# PCM2904DAC_ADC.net
KiCad netlist of a schematic drawn in EAGLE
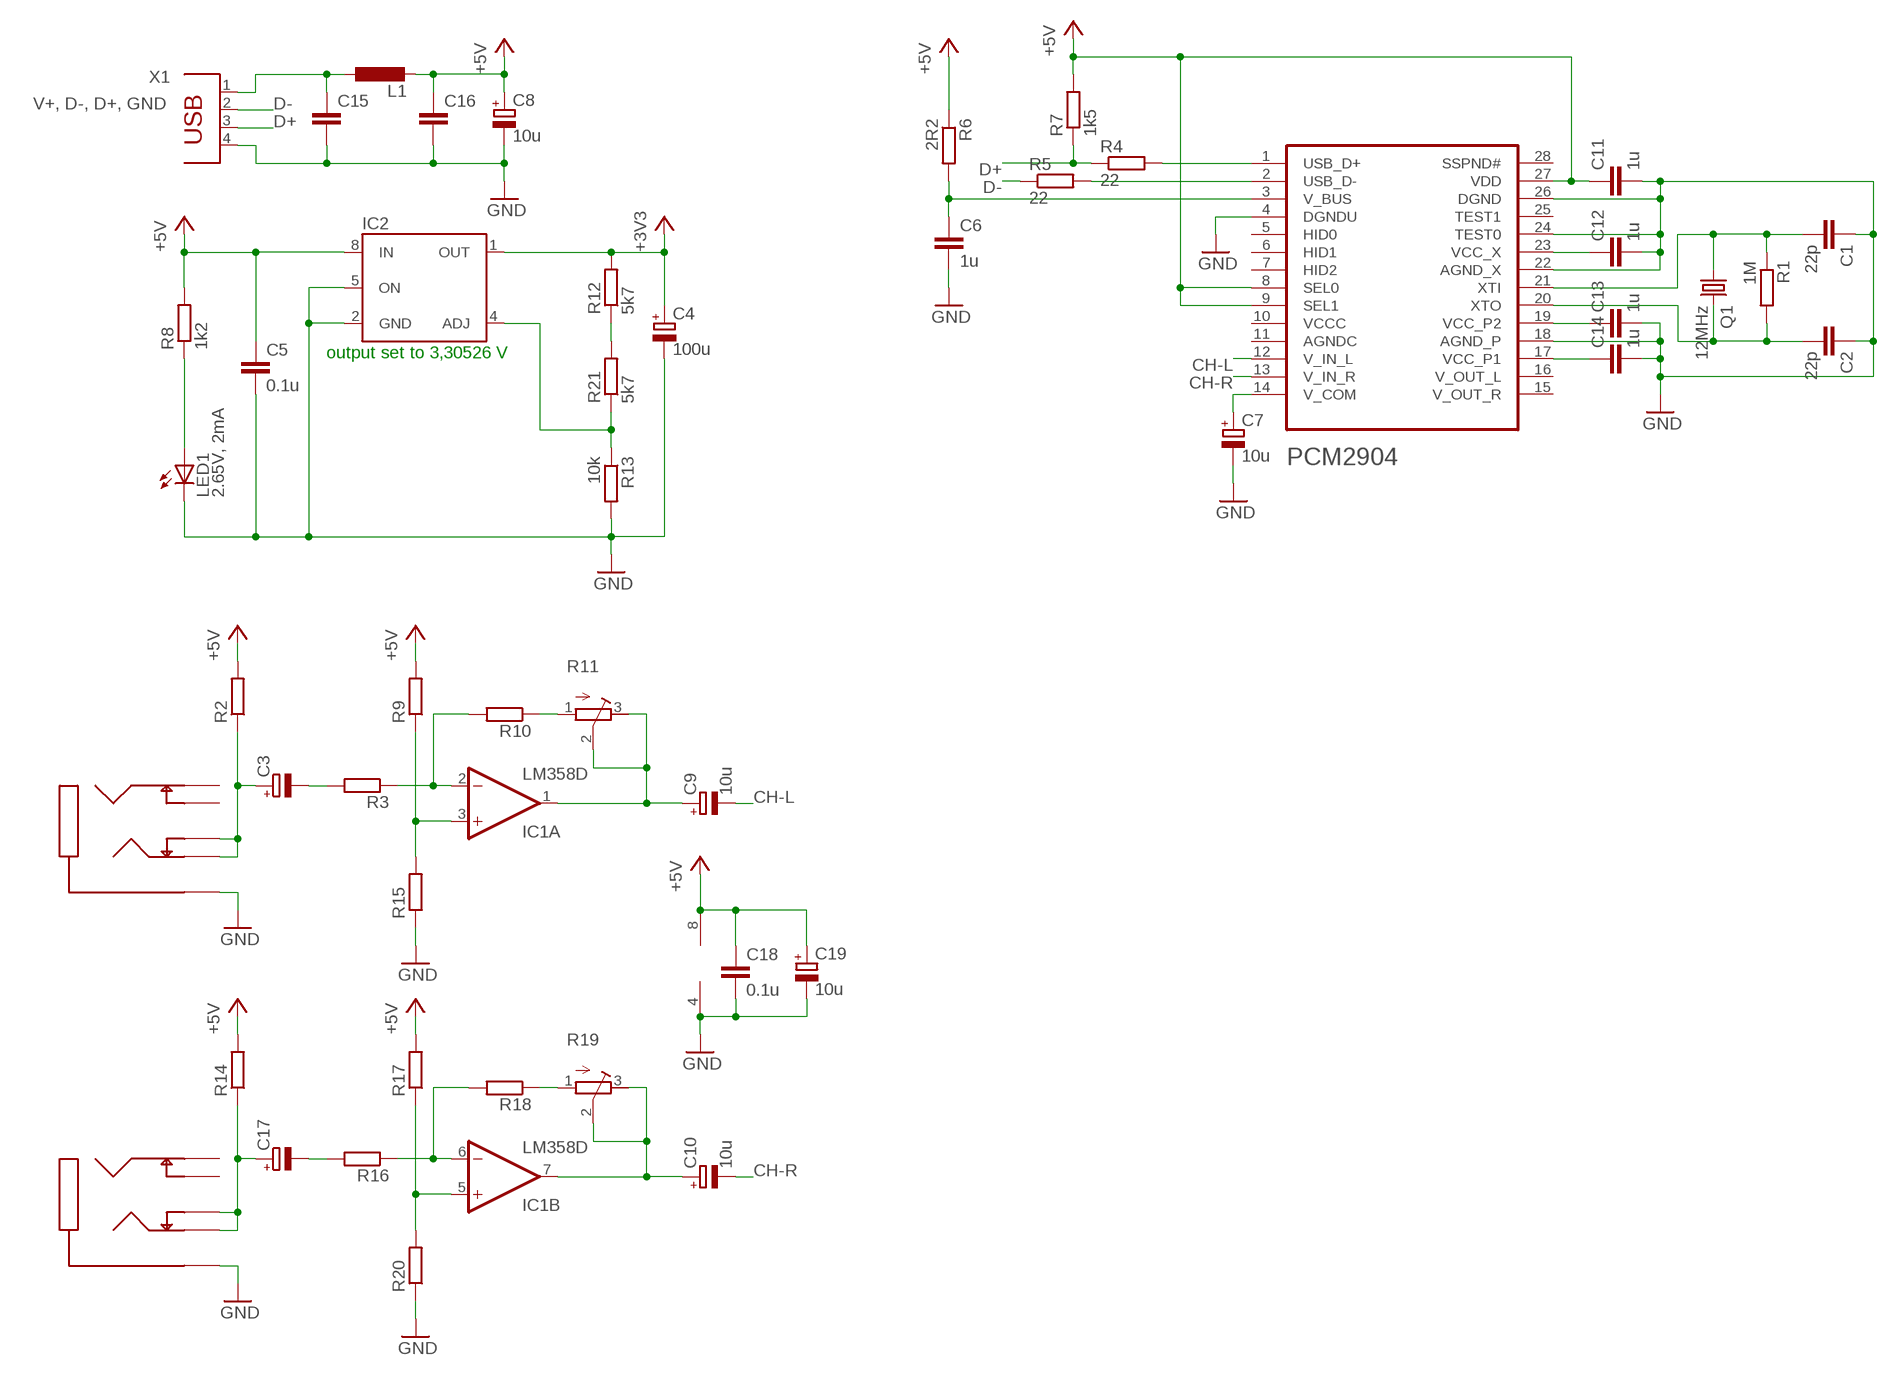
[diagram p0: schematic, sheet 1]

(export (version "E")
  (design (tool "Eeschema 10.0.6"))
  (components
    (comp (ref "C1")
      (value "22p")
      (footprint "eagle-import:C1206")
      (libsource (lib "eagle-import") (part "C-EUC1206"))
    )
    (comp (ref "C2")
      (value "22p")
      (footprint "eagle-import:C1206")
      (libsource (lib "eagle-import") (part "C-EUC1206"))
    )
    (comp (ref "C3")
      (value "CPOL-EU153CLV-0505")
      (footprint "eagle-import:153CLV-0505")
      (libsource (lib "eagle-import") (part "CPOL-EU153CLV-0505"))
    )
    (comp (ref "C4")
      (value "100u")
      (footprint "eagle-import:153CLV-0807")
      (libsource (lib "eagle-import") (part "rcl_334_CPOL-EU153CLV-0807"))
    )
    (comp (ref "C5")
      (value "0.1u")
      (footprint "eagle-import:C1206")
      (libsource (lib "eagle-import") (part "C-EUC1206"))
    )
    (comp (ref "C6")
      (value "1u")
      (footprint "eagle-import:C1206")
      (libsource (lib "eagle-import") (part "C-EUC1206"))
    )
    (comp (ref "C7")
      (value "10u")
      (footprint "eagle-import:153CLV-0505")
      (libsource (lib "eagle-import") (part "rcl_334_CPOL-EU153CLV-0505"))
    )
    (comp (ref "C8")
      (value "10u")
      (footprint "eagle-import:153CLV-0505")
      (libsource (lib "eagle-import") (part "CPOL-EU153CLV-0505"))
    )
    (comp (ref "C9")
      (value "10u")
      (footprint "eagle-import:153CLV-0505")
      (libsource (lib "eagle-import") (part "CPOL-EU153CLV-0505"))
    )
    (comp (ref "C10")
      (value "10u")
      (footprint "eagle-import:153CLV-0505")
      (libsource (lib "eagle-import") (part "rcl_334_CPOL-EU153CLV-0505"))
    )
    (comp (ref "C11")
      (value "1u")
      (footprint "eagle-import:C1206")
      (libsource (lib "eagle-import") (part "C-EUC1206"))
    )
    (comp (ref "C12")
      (value "1u")
      (footprint "eagle-import:C1206")
      (libsource (lib "eagle-import") (part "C-EUC1206"))
    )
    (comp (ref "C13")
      (value "1u")
      (footprint "eagle-import:C1206")
      (libsource (lib "eagle-import") (part "C-EUC1206"))
    )
    (comp (ref "C14")
      (value "1u")
      (footprint "eagle-import:C1206")
      (libsource (lib "eagle-import") (part "C-EUC1206"))
    )
    (comp (ref "C15")
      (value "C-EUC1206K")
      (footprint "eagle-import:C1206K")
      (libsource (lib "eagle-import") (part "rcl_334_C-EUC1206K"))
    )
    (comp (ref "C16")
      (value "C-EUC1206K")
      (footprint "eagle-import:C1206K")
      (libsource (lib "eagle-import") (part "rcl_334_C-EUC1206K"))
    )
    (comp (ref "C17")
      (value "CPOL-EU153CLV-0505")
      (footprint "eagle-import:153CLV-0505")
      (libsource (lib "eagle-import") (part "CPOL-EU153CLV-0505"))
    )
    (comp (ref "C18")
      (value "0.1u")
      (footprint "eagle-import:C1206")
      (libsource (lib "eagle-import") (part "C-EUC1206"))
    )
    (comp (ref "C19")
      (value "10u")
      (footprint "eagle-import:153CLV-0505")
      (libsource (lib "eagle-import") (part "rcl_334_CPOL-EU153CLV-0505"))
    )
    (comp (ref "IC1")
      (value "LM358D")
      (footprint "eagle-import:SO08")
      (libsource (lib "eagle-import") (part "LM358D"))
    )
    (comp (ref "IC2")
      (value "LM2931-ADJM")
      (footprint "eagle-import:SO08")
      (libsource (lib "eagle-import") (part "LM2931-ADJM"))
    )
    (comp (ref "L1")
      (value "L-EU0207/7")
      (footprint "eagle-import:0207_7")
      (libsource (lib "eagle-import") (part "L-EU0207/7"))
    )
    (comp (ref "LED1")
      (value "2.65V, 2mA")
      (footprint "eagle-import:CHIPLED_0805")
      (libsource (lib "eagle-import") (part "LEDCHIPLED_0805"))
    )
    (comp (ref "PCM2904")
      (value "PCM2904")
      (footprint "eagle-import:SSOP28")
      (libsource (lib "eagle-import") (part "PCM2904"))
    )
    (comp (ref "Q1")
      (value "12MHz")
      (footprint "eagle-import:HC49U-V")
      (libsource (lib "eagle-import") (part "CRYSTALHC49U-V"))
    )
    (comp (ref "R1")
      (value "1M")
      (footprint "eagle-import:R1206")
      (libsource (lib "eagle-import") (part "R-EU_R1206"))
    )
    (comp (ref "R2")
      (value "R-EU_R1206W")
      (footprint "eagle-import:R1206W")
      (libsource (lib "eagle-import") (part "rcl_334_R-EU_R1206W"))
    )
    (comp (ref "R3")
      (value "R-EU_R1206W")
      (footprint "eagle-import:R1206W")
      (libsource (lib "eagle-import") (part "rcl_334_R-EU_R1206W"))
    )
    (comp (ref "R4")
      (value "22")
      (footprint "eagle-import:R1206")
      (libsource (lib "eagle-import") (part "R-EU_R1206"))
    )
    (comp (ref "R5")
      (value "22")
      (footprint "eagle-import:R1206")
      (libsource (lib "eagle-import") (part "R-EU_R1206"))
    )
    (comp (ref "R6")
      (value "2R2")
      (footprint "eagle-import:R1206")
      (libsource (lib "eagle-import") (part "R-EU_R1206"))
    )
    (comp (ref "R7")
      (value "1k5")
      (footprint "eagle-import:R1206")
      (libsource (lib "eagle-import") (part "R-EU_R1206"))
    )
    (comp (ref "R8")
      (value "1k2")
      (footprint "eagle-import:R1206")
      (libsource (lib "eagle-import") (part "R-EU_R1206"))
    )
    (comp (ref "R9")
      (value "R-EU_R1206W")
      (footprint "eagle-import:R1206W")
      (libsource (lib "eagle-import") (part "rcl_334_R-EU_R1206W"))
    )
    (comp (ref "R10")
      (value "R-EU_R1206W")
      (footprint "eagle-import:R1206W")
      (libsource (lib "eagle-import") (part "rcl_334_R-EU_R1206W"))
    )
    (comp (ref "R11")
      (value "R-TRIMM64W")
      (footprint "eagle-import:RTRIM64W")
      (libsource (lib "eagle-import") (part "R-TRIMM64W"))
    )
    (comp (ref "R12")
      (value "5k7")
      (footprint "eagle-import:R1206")
      (libsource (lib "eagle-import") (part "R-EU_R1206"))
    )
    (comp (ref "R13")
      (value "10k")
      (footprint "eagle-import:R1206")
      (libsource (lib "eagle-import") (part "R-EU_R1206"))
    )
    (comp (ref "R14")
      (value "R-EU_R1206W")
      (footprint "eagle-import:R1206W")
      (libsource (lib "eagle-import") (part "rcl_334_R-EU_R1206W"))
    )
    (comp (ref "R15")
      (value "R-EU_R1206W")
      (footprint "eagle-import:R1206W")
      (libsource (lib "eagle-import") (part "rcl_334_R-EU_R1206W"))
    )
    (comp (ref "R16")
      (value "R-EU_R1206W")
      (footprint "eagle-import:R1206W")
      (libsource (lib "eagle-import") (part "rcl_334_R-EU_R1206W"))
    )
    (comp (ref "R17")
      (value "R-EU_R1206W")
      (footprint "eagle-import:R1206W")
      (libsource (lib "eagle-import") (part "rcl_334_R-EU_R1206W"))
    )
    (comp (ref "R18")
      (value "R-EU_R1206W")
      (footprint "eagle-import:R1206W")
      (libsource (lib "eagle-import") (part "rcl_334_R-EU_R1206W"))
    )
    (comp (ref "R19")
      (value "R-TRIMM64W")
      (footprint "eagle-import:RTRIM64W")
      (libsource (lib "eagle-import") (part "R-TRIMM64W"))
    )
    (comp (ref "R20")
      (value "R-EU_R1206W")
      (footprint "eagle-import:R1206W")
      (libsource (lib "eagle-import") (part "rcl_334_R-EU_R1206W"))
    )
    (comp (ref "R21")
      (value "5k7")
      (footprint "eagle-import:R1206")
      (libsource (lib "eagle-import") (part "R-EU_R1206"))
    )
    (comp (ref "U$1")
      (value "1/8STEREO")
      (footprint "eagle-import:1_8STEREO")
      (libsource (lib "eagle-import") (part "1/8STEREO"))
    )
    (comp (ref "U$8")
      (value "1/8STEREO")
      (footprint "eagle-import:1_8STEREO")
      (libsource (lib "eagle-import") (part "1/8STEREO"))
    )
    (comp (ref "X1")
      (value "V+, D-, D+, GND")
      (footprint "eagle-import:PN61729")
      (libsource (lib "eagle-import") (part "PN61729"))
    )
  )
  (nets
    (net (code "1") (name "+3V3") (class "Default")
      (node (ref "C4") (pin "+") (pinfunction "+_+") (pintype "passive"))
      (node (ref "IC2") (pin "1") (pinfunction "OUT_1") (pintype "output"))
      (node (ref "R12") (pin "2") (pinfunction "2_2") (pintype "passive"))
    )
    (net (code "2") (name "+5V") (class "Default")
      (node (ref "C11") (pin "1") (pinfunction "1_1") (pintype "passive"))
      (node (ref "C16") (pin "1") (pinfunction "1_1") (pintype "passive"))
      (node (ref "C18") (pin "1") (pinfunction "1_1") (pintype "passive"))
      (node (ref "C19") (pin "+") (pinfunction "+_+") (pintype "passive"))
      (node (ref "C5") (pin "1") (pinfunction "1_1") (pintype "passive"))
      (node (ref "C8") (pin "+") (pinfunction "+_+") (pintype "passive"))
      (node (ref "IC1") (pin "8") (pinfunction "V+_8") (pintype "power_in"))
      (node (ref "IC2") (pin "8") (pinfunction "IN_8") (pintype "power_in"))
      (node (ref "L1") (pin "2") (pinfunction "2_2") (pintype "passive"))
      (node (ref "PCM2904") (pin "27") (pinfunction "VDD_27") (pintype "bidirectional"))
      (node (ref "PCM2904") (pin "8") (pinfunction "SEL0_8") (pintype "bidirectional"))
      (node (ref "PCM2904") (pin "9") (pinfunction "SEL1_9") (pintype "bidirectional"))
      (node (ref "R14") (pin "2") (pinfunction "2_2") (pintype "passive"))
      (node (ref "R17") (pin "2") (pinfunction "2_2") (pintype "passive"))
      (node (ref "R2") (pin "2") (pinfunction "2_2") (pintype "passive"))
      (node (ref "R6") (pin "1") (pinfunction "1_1") (pintype "passive"))
      (node (ref "R7") (pin "2") (pinfunction "2_2") (pintype "passive"))
      (node (ref "R8") (pin "2") (pinfunction "2_2") (pintype "passive"))
      (node (ref "R9") (pin "2") (pinfunction "2_2") (pintype "passive"))
    )
    (net (code "3") (name "/CH-L") (class "Default")
      (node (ref "C9") (pin "-") (pinfunction "-_-") (pintype "passive"))
      (node (ref "PCM2904") (pin "12") (pinfunction "V_IN_L_12") (pintype "input"))
    )
    (net (code "4") (name "/CH-R") (class "Default")
      (node (ref "C10") (pin "-") (pinfunction "-_-") (pintype "passive"))
      (node (ref "PCM2904") (pin "13") (pinfunction "V_IN_R_13") (pintype "input"))
    )
    (net (code "5") (name "/D+") (class "Default")
      (node (ref "R4") (pin "1") (pinfunction "1_1") (pintype "passive"))
      (node (ref "R7") (pin "1") (pinfunction "1_1") (pintype "passive"))
      (node (ref "X1") (pin "3") (pinfunction "3_3") (pintype "passive"))
    )
    (net (code "6") (name "/D-") (class "Default")
      (node (ref "R5") (pin "1") (pinfunction "1_1") (pintype "passive"))
      (node (ref "X1") (pin "2") (pinfunction "2_2") (pintype "passive"))
    )
    (net (code "7") (name "GND") (class "Default")
      (node (ref "C1") (pin "1") (pinfunction "1_1") (pintype "passive"))
      (node (ref "C11") (pin "2") (pinfunction "2_2") (pintype "passive"))
      (node (ref "C12") (pin "2") (pinfunction "2_2") (pintype "passive"))
      (node (ref "C13") (pin "2") (pinfunction "2_2") (pintype "passive"))
      (node (ref "C14") (pin "2") (pinfunction "2_2") (pintype "passive"))
      (node (ref "C15") (pin "2") (pinfunction "2_2") (pintype "passive"))
      (node (ref "C16") (pin "2") (pinfunction "2_2") (pintype "passive"))
      (node (ref "C18") (pin "2") (pinfunction "2_2") (pintype "passive"))
      (node (ref "C19") (pin "-") (pinfunction "-_-") (pintype "passive"))
      (node (ref "C2") (pin "1") (pinfunction "1_1") (pintype "passive"))
      (node (ref "C4") (pin "-") (pinfunction "-_-") (pintype "passive"))
      (node (ref "C5") (pin "2") (pinfunction "2_2") (pintype "passive"))
      (node (ref "C6") (pin "2") (pinfunction "2_2") (pintype "passive"))
      (node (ref "C7") (pin "-") (pinfunction "-_-") (pintype "passive"))
      (node (ref "C8") (pin "-") (pinfunction "-_-") (pintype "passive"))
      (node (ref "IC1") (pin "4") (pinfunction "V-_4") (pintype "power_in"))
      (node (ref "IC2") (pin "2") (pinfunction "GND_2") (pintype "power_in"))
      (node (ref "IC2") (pin "5") (pinfunction "ON_5") (pintype "input"))
      (node (ref "LED1") (pin "C") (pinfunction "C_C") (pintype "passive"))
      (node (ref "PCM2904") (pin "18") (pinfunction "AGND_P_18") (pintype "bidirectional"))
      (node (ref "PCM2904") (pin "22") (pinfunction "AGND_X_22") (pintype "bidirectional"))
      (node (ref "PCM2904") (pin "24") (pinfunction "TEST0_24") (pintype "bidirectional"))
      (node (ref "PCM2904") (pin "26") (pinfunction "DGND_26") (pintype "bidirectional"))
      (node (ref "PCM2904") (pin "4") (pinfunction "DGNDU_4") (pintype "bidirectional"))
      (node (ref "R13") (pin "2") (pinfunction "2_2") (pintype "passive"))
      (node (ref "R15") (pin "1") (pinfunction "1_1") (pintype "passive"))
      (node (ref "R20") (pin "1") (pinfunction "1_1") (pintype "passive"))
      (node (ref "U$1") (pin "P$1") (pinfunction "P$1_P$1") (pintype "bidirectional"))
      (node (ref "U$8") (pin "P$1") (pinfunction "P$1_P$1") (pintype "bidirectional"))
      (node (ref "X1") (pin "4") (pinfunction "4_4") (pintype "passive"))
    )
    (net (code "8") (name "Net-(C3-Pad+)") (class "Default")
      (node (ref "C3") (pin "+") (pinfunction "+_+") (pintype "passive"))
      (node (ref "R2") (pin "1") (pinfunction "1_1") (pintype "passive"))
      (node (ref "U$8") (pin "P$4") (pinfunction "P$4_P$4") (pintype "bidirectional"))
      (node (ref "U$8") (pin "P$5") (pinfunction "P$5_P$5") (pintype "bidirectional"))
    )
    (net (code "9") (name "Net-(C3-Pad-)") (class "Default")
      (node (ref "C3") (pin "-") (pinfunction "-_-") (pintype "passive"))
      (node (ref "R3") (pin "2") (pinfunction "2_2") (pintype "passive"))
    )
    (net (code "10") (name "Net-(C15-Pad1)") (class "Default")
      (node (ref "C15") (pin "1") (pinfunction "1_1") (pintype "passive"))
      (node (ref "L1") (pin "1") (pinfunction "1_1") (pintype "passive"))
      (node (ref "X1") (pin "1") (pinfunction "1_1") (pintype "passive"))
    )
    (net (code "11") (name "Net-(C17-Pad+)") (class "Default")
      (node (ref "C17") (pin "+") (pinfunction "+_+") (pintype "passive"))
      (node (ref "R14") (pin "1") (pinfunction "1_1") (pintype "passive"))
      (node (ref "U$1") (pin "P$4") (pinfunction "P$4_P$4") (pintype "bidirectional"))
      (node (ref "U$1") (pin "P$5") (pinfunction "P$5_P$5") (pintype "bidirectional"))
    )
    (net (code "12") (name "Net-(C17-Pad-)") (class "Default")
      (node (ref "C17") (pin "-") (pinfunction "-_-") (pintype "passive"))
      (node (ref "R16") (pin "2") (pinfunction "2_2") (pintype "passive"))
    )
    (net (code "13") (name "Net-(IC1A-+IN)") (class "Default")
      (node (ref "IC1") (pin "3") (pinfunction "+IN_3") (pintype "input"))
      (node (ref "R15") (pin "2") (pinfunction "2_2") (pintype "passive"))
      (node (ref "R9") (pin "1") (pinfunction "1_1") (pintype "passive"))
    )
    (net (code "14") (name "Net-(IC1A--IN)") (class "Default")
      (node (ref "IC1") (pin "2") (pinfunction "-IN_2") (pintype "input"))
      (node (ref "R10") (pin "2") (pinfunction "2_2") (pintype "passive"))
      (node (ref "R3") (pin "1") (pinfunction "1_1") (pintype "passive"))
    )
    (net (code "15") (name "Net-(IC1A-OUT)") (class "Default")
      (node (ref "C9") (pin "+") (pinfunction "+_+") (pintype "passive"))
      (node (ref "IC1") (pin "1") (pinfunction "OUT_1") (pintype "output"))
      (node (ref "R11") (pin "2") (pinfunction "S_2") (pintype "passive"))
      (node (ref "R11") (pin "3") (pinfunction "E_3") (pintype "passive"))
    )
    (net (code "16") (name "Net-(IC1B-+IN)") (class "Default")
      (node (ref "IC1") (pin "5") (pinfunction "+IN_5") (pintype "input"))
      (node (ref "R17") (pin "1") (pinfunction "1_1") (pintype "passive"))
      (node (ref "R20") (pin "2") (pinfunction "2_2") (pintype "passive"))
    )
    (net (code "17") (name "Net-(IC1B--IN)") (class "Default")
      (node (ref "IC1") (pin "6") (pinfunction "-IN_6") (pintype "input"))
      (node (ref "R16") (pin "1") (pinfunction "1_1") (pintype "passive"))
      (node (ref "R18") (pin "2") (pinfunction "2_2") (pintype "passive"))
    )
    (net (code "18") (name "Net-(IC1B-OUT)") (class "Default")
      (node (ref "C10") (pin "+") (pinfunction "+_+") (pintype "passive"))
      (node (ref "IC1") (pin "7") (pinfunction "OUT_7") (pintype "output"))
      (node (ref "R19") (pin "2") (pinfunction "S_2") (pintype "passive"))
      (node (ref "R19") (pin "3") (pinfunction "E_3") (pintype "passive"))
    )
    (net (code "19") (name "Net-(IC2-ADJ)") (class "Default")
      (node (ref "IC2") (pin "4") (pinfunction "ADJ_4") (pintype "input"))
      (node (ref "R13") (pin "1") (pinfunction "1_1") (pintype "passive"))
      (node (ref "R21") (pin "1") (pinfunction "1_1") (pintype "passive"))
    )
    (net (code "20") (name "Net-(LED1-PadA)") (class "Default")
      (node (ref "LED1") (pin "A") (pinfunction "A_A") (pintype "passive"))
      (node (ref "R8") (pin "1") (pinfunction "1_1") (pintype "passive"))
    )
    (net (code "21") (name "Net-(PCM2904-USB_D+)") (class "Default")
      (node (ref "PCM2904") (pin "1") (pinfunction "USB_D+_1") (pintype "bidirectional"))
      (node (ref "R4") (pin "2") (pinfunction "2_2") (pintype "passive"))
    )
    (net (code "22") (name "Net-(PCM2904-USB_D-)") (class "Default")
      (node (ref "PCM2904") (pin "2") (pinfunction "USB_D-_2") (pintype "bidirectional"))
      (node (ref "R5") (pin "2") (pinfunction "2_2") (pintype "passive"))
    )
    (net (code "23") (name "Net-(PCM2904-VCC_P1)") (class "Default")
      (node (ref "C14") (pin "1") (pinfunction "1_1") (pintype "passive"))
      (node (ref "PCM2904") (pin "17") (pinfunction "VCC_P1_17") (pintype "bidirectional"))
    )
    (net (code "24") (name "Net-(PCM2904-VCC_P2)") (class "Default")
      (node (ref "C13") (pin "1") (pinfunction "1_1") (pintype "passive"))
      (node (ref "PCM2904") (pin "19") (pinfunction "VCC_P2_19") (pintype "bidirectional"))
    )
    (net (code "25") (name "Net-(PCM2904-VCC_X)") (class "Default")
      (node (ref "C12") (pin "1") (pinfunction "1_1") (pintype "passive"))
      (node (ref "PCM2904") (pin "23") (pinfunction "VCC_X_23") (pintype "bidirectional"))
    )
    (net (code "26") (name "Net-(PCM2904-V_BUS)") (class "Default")
      (node (ref "C6") (pin "1") (pinfunction "1_1") (pintype "passive"))
      (node (ref "PCM2904") (pin "3") (pinfunction "V_BUS_3") (pintype "bidirectional"))
      (node (ref "R6") (pin "2") (pinfunction "2_2") (pintype "passive"))
    )
    (net (code "27") (name "Net-(PCM2904-V_COM)") (class "Default")
      (node (ref "C7") (pin "+") (pinfunction "+_+") (pintype "passive"))
      (node (ref "PCM2904") (pin "14") (pinfunction "V_COM_14") (pintype "bidirectional"))
    )
    (net (code "28") (name "Net-(PCM2904-XTI)") (class "Default")
      (node (ref "C1") (pin "2") (pinfunction "2_2") (pintype "passive"))
      (node (ref "PCM2904") (pin "21") (pinfunction "XTI_21") (pintype "bidirectional"))
      (node (ref "Q1") (pin "1") (pinfunction "1_1") (pintype "passive"))
      (node (ref "R1") (pin "1") (pinfunction "1_1") (pintype "passive"))
    )
    (net (code "29") (name "Net-(PCM2904-XTO)") (class "Default")
      (node (ref "C2") (pin "2") (pinfunction "2_2") (pintype "passive"))
      (node (ref "PCM2904") (pin "20") (pinfunction "XTO_20") (pintype "bidirectional"))
      (node (ref "Q1") (pin "2") (pinfunction "2_2") (pintype "passive"))
      (node (ref "R1") (pin "2") (pinfunction "2_2") (pintype "passive"))
    )
    (net (code "30") (name "Net-(R11-A)") (class "Default")
      (node (ref "R10") (pin "1") (pinfunction "1_1") (pintype "passive"))
      (node (ref "R11") (pin "1") (pinfunction "A_1") (pintype "passive"))
    )
    (net (code "31") (name "Net-(R12-Pad1)") (class "Default")
      (node (ref "R12") (pin "1") (pinfunction "1_1") (pintype "passive"))
      (node (ref "R21") (pin "2") (pinfunction "2_2") (pintype "passive"))
    )
    (net (code "32") (name "Net-(R19-A)") (class "Default")
      (node (ref "R18") (pin "1") (pinfunction "1_1") (pintype "passive"))
      (node (ref "R19") (pin "1") (pinfunction "A_1") (pintype "passive"))
    )
    (net (code "33") (name "unconnected-(PCM2904-AGNDC-Pad11)") (class "Default")
      (node (ref "PCM2904") (pin "11") (pinfunction "AGNDC_11") (pintype "bidirectional"))
    )
    (net (code "34") (name "unconnected-(PCM2904-HID0-Pad5)") (class "Default")
      (node (ref "PCM2904") (pin "5") (pinfunction "HID0_5") (pintype "bidirectional"))
    )
    (net (code "35") (name "unconnected-(PCM2904-HID1-Pad6)") (class "Default")
      (node (ref "PCM2904") (pin "6") (pinfunction "HID1_6") (pintype "bidirectional"))
    )
    (net (code "36") (name "unconnected-(PCM2904-HID2-Pad7)") (class "Default")
      (node (ref "PCM2904") (pin "7") (pinfunction "HID2_7") (pintype "bidirectional"))
    )
    (net (code "37") (name "unconnected-(PCM2904-SSPND#-Pad28)") (class "Default")
      (node (ref "PCM2904") (pin "28") (pinfunction "SSPND#_28") (pintype "bidirectional"))
    )
    (net (code "38") (name "unconnected-(PCM2904-TEST1-Pad25)") (class "Default")
      (node (ref "PCM2904") (pin "25") (pinfunction "TEST1_25") (pintype "bidirectional"))
    )
    (net (code "39") (name "unconnected-(PCM2904-VCCC-Pad10)") (class "Default")
      (node (ref "PCM2904") (pin "10") (pinfunction "VCCC_10") (pintype "bidirectional"))
    )
    (net (code "40") (name "unconnected-(PCM2904-V_OUT_L-Pad16)") (class "Default")
      (node (ref "PCM2904") (pin "16") (pinfunction "V_OUT_L_16") (pintype "output"))
    )
    (net (code "41") (name "unconnected-(PCM2904-V_OUT_R-Pad15)") (class "Default")
      (node (ref "PCM2904") (pin "15") (pinfunction "V_OUT_R_15") (pintype "output"))
    )
    (net (code "42") (name "unconnected-(U$1-PadP$2)") (class "Default")
      (node (ref "U$1") (pin "P$2") (pinfunction "P$2_P$2") (pintype "bidirectional"))
    )
    (net (code "43") (name "unconnected-(U$1-PadP$3)") (class "Default")
      (node (ref "U$1") (pin "P$3") (pinfunction "P$3_P$3") (pintype "bidirectional"))
    )
    (net (code "44") (name "unconnected-(U$8-PadP$2)") (class "Default")
      (node (ref "U$8") (pin "P$2") (pinfunction "P$2_P$2") (pintype "bidirectional"))
    )
    (net (code "45") (name "unconnected-(U$8-PadP$3)") (class "Default")
      (node (ref "U$8") (pin "P$3") (pinfunction "P$3_P$3") (pintype "bidirectional"))
    )
  )
)
